# DCSource6V0.net
KiCad netlist of a schematic drawn in Altium Designer
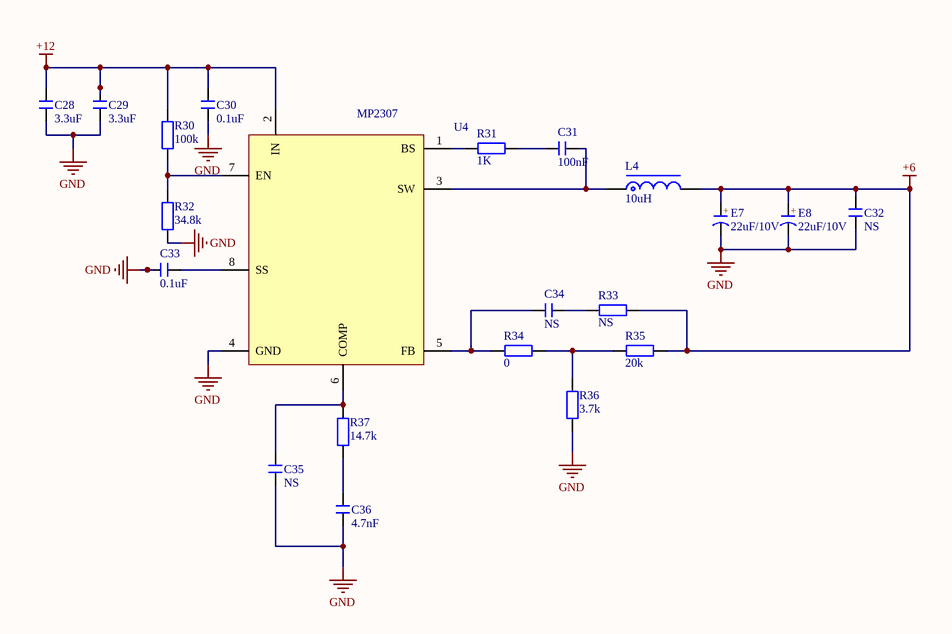
[diagram p0: DCSource6V0.SchDoc]

(export (version "E")
  (design (tool "Eeschema 10.0.6"))
  (components
    (comp (ref "C28")
      (value "3.3uF")
      (footprint "C 0805_L")
      (description "无极性贴片电容")
      (libsource (lib "电容-电阻-电感-电位器") (part "C"))
    )
    (comp (ref "C29")
      (value "3.3uF")
      (footprint "C 0805_L")
      (description "无极性贴片电容")
      (libsource (lib "电容-电阻-电感-电位器") (part "C"))
    )
    (comp (ref "C30")
      (value "0.1uF")
      (footprint "C 0805_L")
      (description "无极性贴片电容")
      (libsource (lib "电容-电阻-电感-电位器") (part "C"))
    )
    (comp (ref "C31")
      (value "100nF")
      (footprint "C 0805_L")
      (description "无极性贴片电容")
      (libsource (lib "电容-电阻-电感-电位器") (part "C"))
    )
    (comp (ref "C32")
      (value "NS")
      (footprint "C 0805_L")
      (description "无极性贴片电容")
      (libsource (lib "电容-电阻-电感-电位器") (part "C"))
    )
    (comp (ref "C33")
      (value "0.1uF")
      (footprint "C 0805_L")
      (description "无极性贴片电容")
      (libsource (lib "电容-电阻-电感-电位器") (part "C"))
    )
    (comp (ref "C34")
      (value "NS")
      (footprint "C 0805_L")
      (description "无极性贴片电容")
      (libsource (lib "电容-电阻-电感-电位器") (part "C"))
    )
    (comp (ref "C35")
      (value "NS")
      (footprint "C 0805_L")
      (description "无极性贴片电容")
      (libsource (lib "电容-电阻-电感-电位器") (part "C"))
    )
    (comp (ref "C36")
      (value "4.7nF")
      (footprint "C 0805_L")
      (description "无极性贴片电容")
      (libsource (lib "电容-电阻-电感-电位器") (part "C"))
    )
    (comp (ref "E7")
      (value "22uF/10V")
      (footprint "CT 5*6 - C")
      (description "贴片固态电容")
      (libsource (lib "电容-电阻-电感-电位器") (part "C-CT"))
    )
    (comp (ref "E8")
      (value "22uF/10V")
      (footprint "CT 5*6 - C")
      (description "贴片固态电容")
      (libsource (lib "电容-电阻-电感-电位器") (part "C-CT"))
    )
    (comp (ref "L4")
      (value "10uH")
      (footprint "CD31")
      (description "贴片功率电感")
      (libsource (lib "电容-电阻-电感-电位器") (part "L-CD"))
    )
    (comp (ref "R30")
      (value "100k")
      (footprint "R 0805_L")
      (description "贴片电阻")
      (libsource (lib "电容-电阻-电感-电位器") (part "R"))
    )
    (comp (ref "R31")
      (value "1K")
      (footprint "R 0805_L")
      (description "贴片电阻")
      (libsource (lib "电容-电阻-电感-电位器") (part "R"))
    )
    (comp (ref "R32")
      (value "34.8k")
      (footprint "R 0805_L")
      (description "贴片电阻")
      (libsource (lib "电容-电阻-电感-电位器") (part "R"))
    )
    (comp (ref "R33")
      (value "NS")
      (footprint "R 0805_L")
      (description "贴片电阻")
      (libsource (lib "电容-电阻-电感-电位器") (part "R"))
    )
    (comp (ref "R34")
      (value "0")
      (footprint "R 0805_L")
      (description "贴片电阻")
      (libsource (lib "电容-电阻-电感-电位器") (part "R"))
    )
    (comp (ref "R35")
      (value "20k")
      (footprint "R 0805_L")
      (description "贴片电阻")
      (libsource (lib "电容-电阻-电感-电位器") (part "R"))
    )
    (comp (ref "R36")
      (value "3.7k")
      (footprint "R 0805_L")
      (description "贴片电阻")
      (libsource (lib "电容-电阻-电感-电位器") (part "R"))
    )
    (comp (ref "R37")
      (value "14.7k")
      (footprint "R 0805_L")
      (description "贴片电阻")
      (libsource (lib "电容-电阻-电感-电位器") (part "R"))
    )
    (comp (ref "U4") (value "MP2307") (footprint "SOP8_M") (libsource (lib "Schlib1") (part "Component_1")))
  )
  (nets
    (net (code "1") (name "+6") (class "Default")
      (node (ref "C32") (pin "2") (pinfunction "2_2") (pintype "passive"))
      (node (ref "E7") (pin "1") (pinfunction "A_1") (pintype "passive"))
      (node (ref "E8") (pin "1") (pinfunction "A_1") (pintype "passive"))
      (node (ref "L4") (pin "2") (pinfunction "2_2") (pintype "passive"))
      (node (ref "R33") (pin "1") (pinfunction "1_1") (pintype "passive"))
      (node (ref "R35") (pin "2") (pinfunction "2_2") (pintype "passive"))
    )
    (net (code "2") (name "+12") (class "Default")
      (node (ref "C28") (pin "2") (pinfunction "2_2") (pintype "passive"))
      (node (ref "C29") (pin "2") (pinfunction "2_2") (pintype "passive"))
      (node (ref "C30") (pin "2") (pinfunction "2_2") (pintype "passive"))
      (node (ref "R30") (pin "2") (pinfunction "2_2") (pintype "passive"))
      (node (ref "U4") (pin "2") (pinfunction "IN_2") (pintype "passive"))
    )
    (net (code "3") (name "GND") (class "Default")
      (node (ref "C28") (pin "1") (pinfunction "1_1") (pintype "passive"))
      (node (ref "C29") (pin "1") (pinfunction "1_1") (pintype "passive"))
      (node (ref "C30") (pin "1") (pinfunction "1_1") (pintype "passive"))
      (node (ref "C32") (pin "1") (pinfunction "1_1") (pintype "passive"))
      (node (ref "C33") (pin "2") (pinfunction "2_2") (pintype "passive"))
      (node (ref "C35") (pin "1") (pinfunction "1_1") (pintype "passive"))
      (node (ref "C36") (pin "1") (pinfunction "1_1") (pintype "passive"))
      (node (ref "E7") (pin "2") (pinfunction "K_2") (pintype "passive"))
      (node (ref "E8") (pin "2") (pinfunction "K_2") (pintype "passive"))
      (node (ref "R32") (pin "1") (pinfunction "1_1") (pintype "passive"))
      (node (ref "R36") (pin "1") (pinfunction "1_1") (pintype "passive"))
      (node (ref "U4") (pin "4") (pinfunction "GND_4") (pintype "passive"))
    )
    (net (code "4") (name "Net-(C31-Pad1)") (class "Default")
      (node (ref "C31") (pin "1") (pinfunction "1_1") (pintype "passive"))
      (node (ref "R31") (pin "2") (pinfunction "2_2") (pintype "passive"))
    )
    (net (code "5") (name "Net-(C34-Pad2)") (class "Default")
      (node (ref "C34") (pin "2") (pinfunction "2_2") (pintype "passive"))
      (node (ref "R33") (pin "2") (pinfunction "2_2") (pintype "passive"))
    )
    (net (code "6") (name "Net-(C36-Pad2)") (class "Default")
      (node (ref "C36") (pin "2") (pinfunction "2_2") (pintype "passive"))
      (node (ref "R37") (pin "1") (pinfunction "1_1") (pintype "passive"))
    )
    (net (code "7") (name "Net-(R34-Pad2)") (class "Default")
      (node (ref "R34") (pin "2") (pinfunction "2_2") (pintype "passive"))
      (node (ref "R35") (pin "1") (pinfunction "1_1") (pintype "passive"))
      (node (ref "R36") (pin "2") (pinfunction "2_2") (pintype "passive"))
    )
    (net (code "8") (name "Net-(U4-BS)") (class "Default")
      (node (ref "R31") (pin "1") (pinfunction "1_1") (pintype "passive"))
      (node (ref "U4") (pin "1") (pinfunction "BS_1") (pintype "passive"))
    )
    (net (code "9") (name "Net-(U4-COMP)") (class "Default")
      (node (ref "C35") (pin "2") (pinfunction "2_2") (pintype "passive"))
      (node (ref "R37") (pin "2") (pinfunction "2_2") (pintype "passive"))
      (node (ref "U4") (pin "6") (pinfunction "COMP_6") (pintype "passive"))
    )
    (net (code "10") (name "Net-(U4-EN)") (class "Default")
      (node (ref "R30") (pin "1") (pinfunction "1_1") (pintype "passive"))
      (node (ref "R32") (pin "2") (pinfunction "2_2") (pintype "passive"))
      (node (ref "U4") (pin "7") (pinfunction "EN_7") (pintype "passive"))
    )
    (net (code "11") (name "Net-(U4-FB)") (class "Default")
      (node (ref "C34") (pin "1") (pinfunction "1_1") (pintype "passive"))
      (node (ref "R34") (pin "1") (pinfunction "1_1") (pintype "passive"))
      (node (ref "U4") (pin "5") (pinfunction "FB_5") (pintype "passive"))
    )
    (net (code "12") (name "Net-(U4-SS)") (class "Default")
      (node (ref "C33") (pin "1") (pinfunction "1_1") (pintype "passive"))
      (node (ref "U4") (pin "8") (pinfunction "SS_8") (pintype "passive"))
    )
    (net (code "13") (name "Net-(U4-SW)") (class "Default")
      (node (ref "C31") (pin "2") (pinfunction "2_2") (pintype "passive"))
      (node (ref "L4") (pin "1") (pinfunction "1_1") (pintype "passive"))
      (node (ref "U4") (pin "3") (pinfunction "SW_3") (pintype "passive"))
    )
  )
)
